# Transmitter_V2.net
KiCad netlist of a schematic drawn in Altium Designer
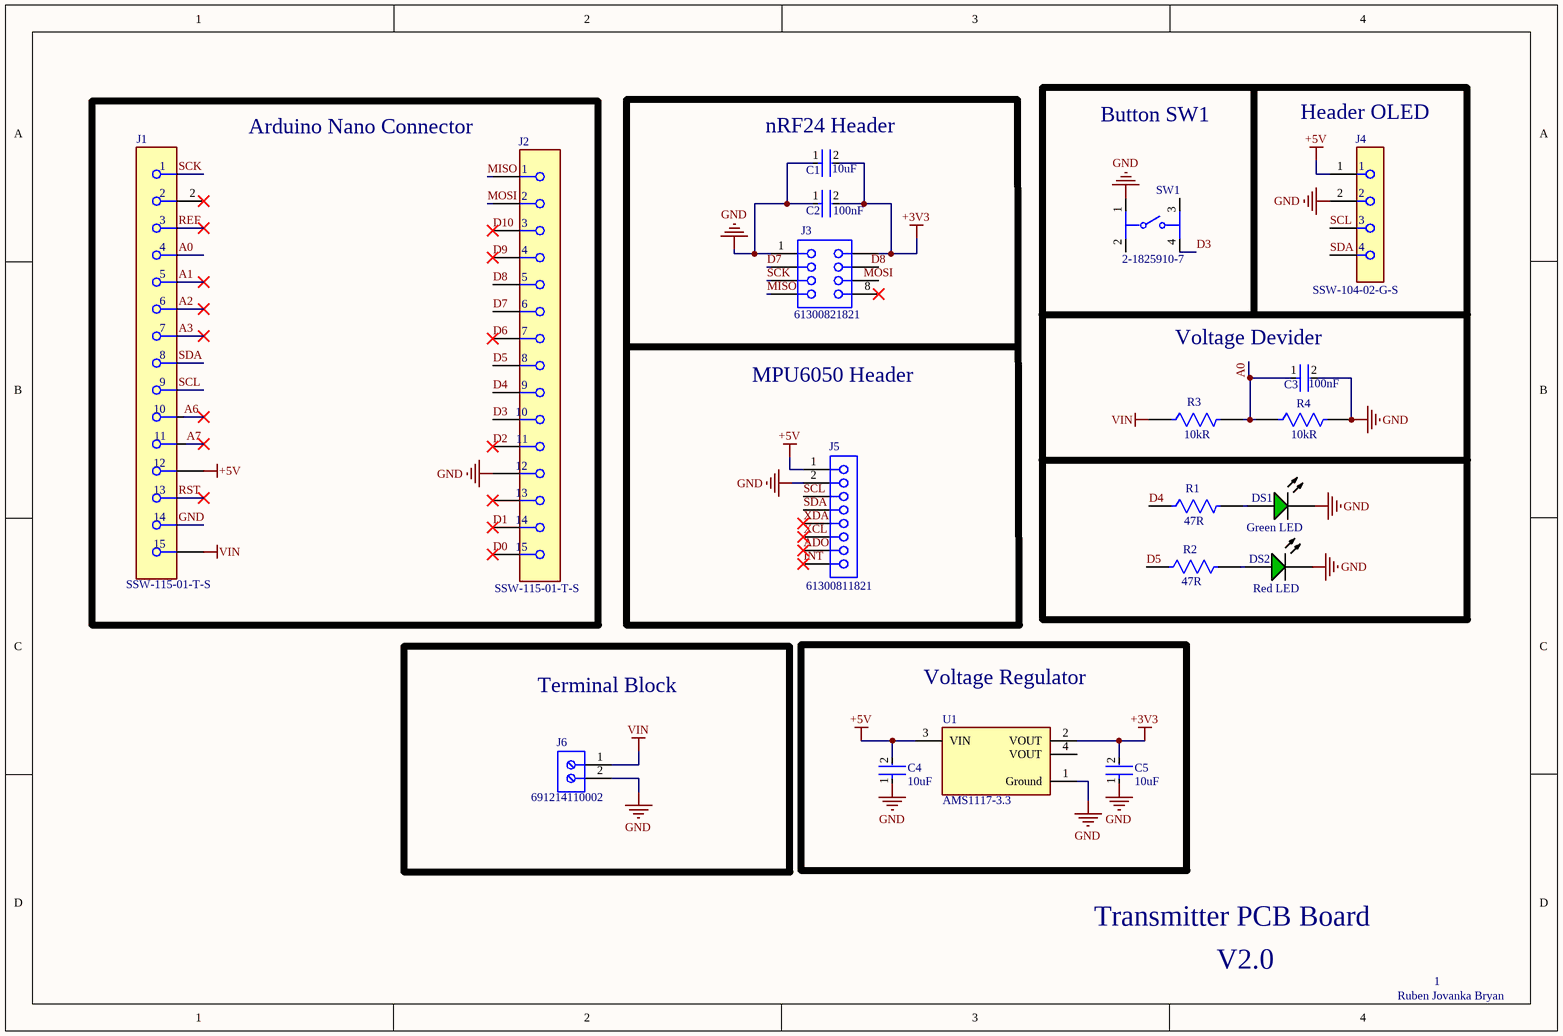
[diagram p0: Transmitter V2.SchDoc]

(export (version "E")
  (design (tool "Eeschema 10.0.6"))
  (components
    (comp (ref "C1")
      (value "10uF")
      (footprint "FP-C0805C-DG-MFG")
      (description "CAP CER 10UF 10V X5R 0805")
      (fields (field (name "TOLERANCE") "10%") (field (name "MANUFACTURER PART NUMBER") "C0805C106K8PACTU"))
      (libsource (lib "Altium Content Vault") (part "11868f565c42a9108669ba33697ecf6"))
    )
    (comp (ref "C2")
      (value "100nF")
      (footprint "FP-CC0805-0_85-MFG")
      (description "CAP CER 0.1UF 16V X7R 0805")
      (fields
        (field (name "MANUFACTURER PART NUMBER") "CC0805KRX7R7BB104")
        (field (name "MANUFACTURER") "Yageo")
      )
      (libsource (lib "Altium Content Vault") (part "11868f565c42a9108669ba33697ecf6"))
    )
    (comp (ref "C3")
      (value "100nF")
      (footprint "FP-CC0805-0_85-MFG")
      (description "CAP CER 0.1UF 16V X7R 0805")
      (fields
        (field (name "MANUFACTURER PART NUMBER") "CC0805KRX7R7BB104")
        (field (name "MANUFACTURER") "Yageo")
      )
      (libsource (lib "Altium Content Vault") (part "11868f565c42a9108669ba33697ecf6"))
    )
    (comp (ref "C4")
      (value "10uF")
      (footprint "FP-C0805C-DG-MFG")
      (description "CAP CER 10UF 10V X5R 0805")
      (fields (field (name "TOLERANCE") "10%") (field (name "MANUFACTURER PART NUMBER") "C0805C106K8PACTU"))
      (libsource (lib "Altium Content Vault") (part "11868f565c42a9108669ba33697ecf6"))
    )
    (comp (ref "C5")
      (value "10uF")
      (footprint "FP-C0805C-DG-MFG")
      (description "CAP CER 10UF 10V X5R 0805")
      (fields (field (name "TOLERANCE") "10%") (field (name "MANUFACTURER PART NUMBER") "C0805C106K8PACTU"))
      (libsource (lib "Altium Content Vault") (part "11868f565c42a9108669ba33697ecf6"))
    )
    (comp (ref "DS1")
      (value "Green LED")
      (footprint "AVAG-HSMX-C170_V")
      (description "Chip LED, Green, 2.2 V, -40 to 85 degC, 2-Pin SMD, Pb-Free, Tape and Reel")
      (fields (field (name "MANUFACTURER") "Avago"))
      (libsource (lib "Altium Content Vault") (part "LED_GREEN_A1K2-2"))
    )
    (comp (ref "DS2")
      (value "Red LED")
      (footprint "AVAG-HSMX-C170_V")
      (description "Chip LED, Green, 2.2 V, -40 to 85 degC, 2-Pin SMD, Pb-Free, Tape and Reel")
      (fields (field (name "MANUFACTURER") "Avago"))
      (libsource (lib "Altium Content Vault") (part "LED_GREEN_A1K2-2"))
    )
    (comp (ref "J1")
      (value "SSW-115-01-T-S")
      (footprint "FP-SSW-115-01-T-S-MFG")
      (description "CONN RCPT 15POS 0.1 TIN PCB")
      (libsource (lib "Altium Content Vault") (part "de2cdd76613f87adcba81301aaab7e9"))
    )
    (comp (ref "J2")
      (value "SSW-115-01-T-S")
      (footprint "FP-SSW-115-01-T-S-MFG")
      (description "CONN RCPT 15POS 0.1 TIN PCB")
      (libsource (lib "") (part "de2cdd76613f87adcba81301aaab7e9_1"))
    )
    (comp (ref "J3")
      (value "61300821821")
      (footprint "61300821821")
      (libsource (lib "Altium Content Vault") (part "Header_Female_2R_08P"))
    )
    (comp (ref "J4")
      (value "SSW-104-02-G-S")
      (footprint "FP-SSW-104-02-G-S-MFG")
      (libsource (lib "Altium Content Vault") (part "56792406a6bd5c25e158f553ecd1aa7"))
    )
    (comp (ref "J5")
      (value "61300811821")
      (footprint "61300811821")
      (libsource (lib "Altium Content Vault") (part "Header_Female_1R_08P"))
    )
    (comp (ref "J6")
      (value "691214110002")
      (footprint "691214110002")
      (fields (field (name "VOLTAGE") "300V"))
      (libsource (lib "Altium Content Vault") (part "TBL - 1R - 02P - Screw"))
    )
    (comp (ref "R1")
      (value "47R")
      (footprint "FP-RC1206-MFG")
      (description "RES SMD 0 OHM JUMPER 1/4W 1206")
      (fields
        (field (name "MANUFACTURER PART NUMBER") "RC1206JR-070RL")
        (field (name "MANUFACTURER") "YAGEO")
      )
      (libsource (lib "Altium Content Vault") (part "1029c3af85768c4190bb7ad29bc67b5"))
    )
    (comp (ref "R2")
      (value "47R")
      (footprint "FP-RC1206-MFG")
      (description "RES SMD 0 OHM JUMPER 1/4W 1206")
      (fields
        (field (name "MANUFACTURER PART NUMBER") "RC1206JR-070RL")
        (field (name "MANUFACTURER") "YAGEO")
      )
      (libsource (lib "Altium Content Vault") (part "1029c3af85768c4190bb7ad29bc67b5"))
    )
    (comp (ref "R3")
      (value "10kR")
      (footprint "FP-RC1206-MFG")
      (description "RES SMD 0 OHM JUMPER 1/4W 1206")
      (fields
        (field (name "MANUFACTURER PART NUMBER") "RC1206JR-070RL")
        (field (name "MANUFACTURER") "YAGEO")
      )
      (libsource (lib "Altium Content Vault") (part "1029c3af85768c4190bb7ad29bc67b5"))
    )
    (comp (ref "R4")
      (value "10kR")
      (footprint "FP-RC1206-MFG")
      (description "RES SMD 0 OHM JUMPER 1/4W 1206")
      (fields
        (field (name "MANUFACTURER PART NUMBER") "RC1206JR-070RL")
        (field (name "MANUFACTURER") "YAGEO")
      )
      (libsource (lib "Altium Content Vault") (part "1029c3af85768c4190bb7ad29bc67b5"))
    )
    (comp (ref "SW1")
      (value "2-1825910-7")
      (footprint "FP-2-1825910-7-MFG")
      (description "SWITCH TACTILE SPST-NO 0.05A 24V")
      (fields
        (field (name "MANUFACTURER") "TE Connectivity")
        (field (name "OCTOPART") "https://octopart.com/2-1825910-7-te+connectivity-42270510")
      )
      (libsource (lib "Altium Content Vault") (part "b8895f3f4cefb76e1819d2863dba89b"))
    )
    (comp (ref "U1")
      (value "AMS1117-3.3")
      (footprint "FP-AMS1117-IPC_C")
      (description "LDO Voltage Regulators 1A, 3.3V")
      (fields
        (field (name "OCTOPART") "https://octopart.com/ams1117-3.3-advanced+monolithic+systems-25899300")
        (field (name "MANUFACTURER") "Advanced Monolithic Systems")
      )
      (libsource (lib "Altium Content Vault") (part "8bdbb5f8e77002000e30dd2845d0354"))
    )
  )
  (nets
    (net (code "1") (name "+3V3") (class "Default")
      (node (ref "C1") (pin "2") (pinfunction "2_2") (pintype "passive"))
      (node (ref "C2") (pin "2") (pinfunction "2_2") (pintype "passive"))
      (node (ref "C5") (pin "2") (pinfunction "2_2") (pintype "passive"))
      (node (ref "J3") (pin "2") (pinfunction "2_2") (pintype "passive"))
      (node (ref "U1") (pin "2") (pinfunction "VOUT_2") (pintype "passive"))
    )
    (net (code "2") (name "+5V") (class "Default")
      (node (ref "C4") (pin "2") (pinfunction "2_2") (pintype "passive"))
      (node (ref "J1") (pin "12") (pinfunction "12_12") (pintype "passive"))
      (node (ref "J4") (pin "1") (pinfunction "1_1") (pintype "passive"))
      (node (ref "J5") (pin "1") (pinfunction "1_1") (pintype "passive"))
      (node (ref "U1") (pin "3") (pinfunction "VIN_3") (pintype "power_in"))
    )
    (net (code "3") (name "/A0") (class "Default")
      (node (ref "C3") (pin "1") (pinfunction "1_1") (pintype "passive"))
      (node (ref "J1") (pin "4") (pinfunction "4_4") (pintype "passive"))
      (node (ref "R3") (pin "2") (pinfunction "2_2") (pintype "passive"))
      (node (ref "R4") (pin "1") (pinfunction "1_1") (pintype "passive"))
    )
    (net (code "4") (name "/A1") (class "Default")
      (node (ref "J1") (pin "5") (pinfunction "5_5") (pintype "passive+no_connect"))
    )
    (net (code "5") (name "/A2") (class "Default")
      (node (ref "J1") (pin "6") (pinfunction "6_6") (pintype "passive+no_connect"))
    )
    (net (code "6") (name "/A3") (class "Default")
      (node (ref "J1") (pin "7") (pinfunction "7_7") (pintype "passive+no_connect"))
    )
    (net (code "7") (name "/A6") (class "Default")
      (node (ref "J1") (pin "10") (pinfunction "10_10") (pintype "passive+no_connect"))
    )
    (net (code "8") (name "/A7") (class "Default")
      (node (ref "J1") (pin "11") (pinfunction "11_11") (pintype "passive+no_connect"))
    )
    (net (code "9") (name "/ADO") (class "Default")
      (node (ref "J5") (pin "7") (pinfunction "7_7") (pintype "passive+no_connect"))
    )
    (net (code "10") (name "/D0") (class "Default")
      (node (ref "J2") (pin "15") (pinfunction "15_15") (pintype "passive+no_connect"))
    )
    (net (code "11") (name "/D1") (class "Default")
      (node (ref "J2") (pin "14") (pinfunction "14_14") (pintype "passive+no_connect"))
    )
    (net (code "12") (name "/D2") (class "Default")
      (node (ref "J2") (pin "11") (pinfunction "11_11") (pintype "passive+no_connect"))
    )
    (net (code "13") (name "/D3") (class "Default")
      (node (ref "J2") (pin "10") (pinfunction "10_10") (pintype "passive"))
      (node (ref "SW1") (pin "4") (pinfunction "4_4") (pintype "passive"))
    )
    (net (code "14") (name "/D4") (class "Default")
      (node (ref "J2") (pin "9") (pinfunction "9_9") (pintype "passive"))
      (node (ref "R1") (pin "1") (pinfunction "1_1") (pintype "passive"))
    )
    (net (code "15") (name "/D5") (class "Default")
      (node (ref "J2") (pin "8") (pinfunction "8_8") (pintype "passive"))
      (node (ref "R2") (pin "1") (pinfunction "1_1") (pintype "passive"))
    )
    (net (code "16") (name "/D6") (class "Default")
      (node (ref "J2") (pin "7") (pinfunction "7_7") (pintype "passive+no_connect"))
    )
    (net (code "17") (name "/D7") (class "Default")
      (node (ref "J2") (pin "6") (pinfunction "6_6") (pintype "passive"))
      (node (ref "J3") (pin "3") (pinfunction "3_3") (pintype "passive"))
    )
    (net (code "18") (name "/D8") (class "Default")
      (node (ref "J2") (pin "5") (pinfunction "5_5") (pintype "passive"))
      (node (ref "J3") (pin "4") (pinfunction "4_4") (pintype "passive"))
    )
    (net (code "19") (name "/D9") (class "Default")
      (node (ref "J2") (pin "4") (pinfunction "4_4") (pintype "passive+no_connect"))
    )
    (net (code "20") (name "/D10") (class "Default")
      (node (ref "J2") (pin "3") (pinfunction "3_3") (pintype "passive+no_connect"))
    )
    (net (code "21") (name "/INT") (class "Default")
      (node (ref "J5") (pin "8") (pinfunction "8_8") (pintype "passive+no_connect"))
    )
    (net (code "22") (name "/MISO") (class "Default")
      (node (ref "J2") (pin "1") (pinfunction "1_1") (pintype "passive"))
      (node (ref "J3") (pin "7") (pinfunction "7_7") (pintype "passive"))
    )
    (net (code "23") (name "/MOSI") (class "Default")
      (node (ref "J2") (pin "2") (pinfunction "2_2") (pintype "passive"))
      (node (ref "J3") (pin "6") (pinfunction "6_6") (pintype "passive"))
    )
    (net (code "24") (name "/REF") (class "Default")
      (node (ref "J1") (pin "3") (pinfunction "3_3") (pintype "passive+no_connect"))
    )
    (net (code "25") (name "/RST") (class "Default")
      (node (ref "J1") (pin "13") (pinfunction "13_13") (pintype "passive+no_connect"))
    )
    (net (code "26") (name "/SCK") (class "Default")
      (node (ref "J1") (pin "1") (pinfunction "1_1") (pintype "passive"))
      (node (ref "J3") (pin "5") (pinfunction "5_5") (pintype "passive"))
    )
    (net (code "27") (name "/SCL") (class "Default")
      (node (ref "J1") (pin "9") (pinfunction "9_9") (pintype "passive"))
      (node (ref "J4") (pin "3") (pinfunction "3_3") (pintype "passive"))
      (node (ref "J5") (pin "3") (pinfunction "3_3") (pintype "passive"))
    )
    (net (code "28") (name "/SDA") (class "Default")
      (node (ref "J1") (pin "8") (pinfunction "8_8") (pintype "passive"))
      (node (ref "J4") (pin "4") (pinfunction "4_4") (pintype "passive"))
      (node (ref "J5") (pin "4") (pinfunction "4_4") (pintype "passive"))
    )
    (net (code "29") (name "/XCL") (class "Default")
      (node (ref "J5") (pin "6") (pinfunction "6_6") (pintype "passive+no_connect"))
    )
    (net (code "30") (name "/XDA") (class "Default")
      (node (ref "J5") (pin "5") (pinfunction "5_5") (pintype "passive+no_connect"))
    )
    (net (code "31") (name "GND") (class "Default")
      (node (ref "C1") (pin "1") (pinfunction "1_1") (pintype "passive"))
      (node (ref "C2") (pin "1") (pinfunction "1_1") (pintype "passive"))
      (node (ref "C3") (pin "2") (pinfunction "2_2") (pintype "passive"))
      (node (ref "C4") (pin "1") (pinfunction "1_1") (pintype "passive"))
      (node (ref "C5") (pin "1") (pinfunction "1_1") (pintype "passive"))
      (node (ref "DS1") (pin "2") (pinfunction "K_2") (pintype "passive"))
      (node (ref "DS2") (pin "2") (pinfunction "K_2") (pintype "passive"))
      (node (ref "J1") (pin "14") (pinfunction "14_14") (pintype "passive"))
      (node (ref "J2") (pin "12") (pinfunction "12_12") (pintype "passive"))
      (node (ref "J3") (pin "1") (pinfunction "1_1") (pintype "passive"))
      (node (ref "J4") (pin "2") (pinfunction "2_2") (pintype "passive"))
      (node (ref "J5") (pin "2") (pinfunction "2_2") (pintype "passive"))
      (node (ref "J6") (pin "2") (pinfunction "2_2") (pintype "passive"))
      (node (ref "R4") (pin "2") (pinfunction "2_2") (pintype "passive"))
      (node (ref "SW1") (pin "1") (pinfunction "1_1") (pintype "passive"))
      (node (ref "U1") (pin "1") (pinfunction "Ground_1") (pintype "power_in"))
    )
    (net (code "32") (name "Net-(DS1-A)") (class "Default")
      (node (ref "DS1") (pin "1") (pinfunction "A_1") (pintype "passive"))
      (node (ref "R1") (pin "2") (pinfunction "2_2") (pintype "passive"))
    )
    (net (code "33") (name "Net-(DS2-A)") (class "Default")
      (node (ref "DS2") (pin "1") (pinfunction "A_1") (pintype "passive"))
      (node (ref "R2") (pin "2") (pinfunction "2_2") (pintype "passive"))
    )
    (net (code "34") (name "VIN") (class "Default")
      (node (ref "J1") (pin "15") (pinfunction "15_15") (pintype "passive"))
      (node (ref "J6") (pin "1") (pinfunction "1_1") (pintype "passive"))
      (node (ref "R3") (pin "1") (pinfunction "1_1") (pintype "passive"))
    )
    (net (code "35") (name "unconnected-(J1-Pad2)") (class "Default")
      (node (ref "J1") (pin "2") (pinfunction "2_2") (pintype "passive+no_connect"))
    )
    (net (code "36") (name "unconnected-(J2-Pad13)") (class "Default")
      (node (ref "J2") (pin "13") (pinfunction "13_13") (pintype "passive+no_connect"))
    )
    (net (code "37") (name "unconnected-(J3-Pad8)") (class "Default")
      (node (ref "J3") (pin "8") (pinfunction "8_8") (pintype "passive+no_connect"))
    )
    (net (code "38") (name "unconnected-(SW1-Pad2)") (class "Default")
      (node (ref "SW1") (pin "2") (pinfunction "2_2") (pintype "passive"))
    )
    (net (code "39") (name "unconnected-(SW1-Pad3)") (class "Default")
      (node (ref "SW1") (pin "3") (pinfunction "3_3") (pintype "passive"))
    )
    (net (code "40") (name "unconnected-(U1-VOUT-Pad4)") (class "Default")
      (node (ref "U1") (pin "4") (pinfunction "VOUT_4") (pintype "passive"))
    )
  )
)
